# JACart2.net
KiCad netlist of a schematic drawn in EAGLE
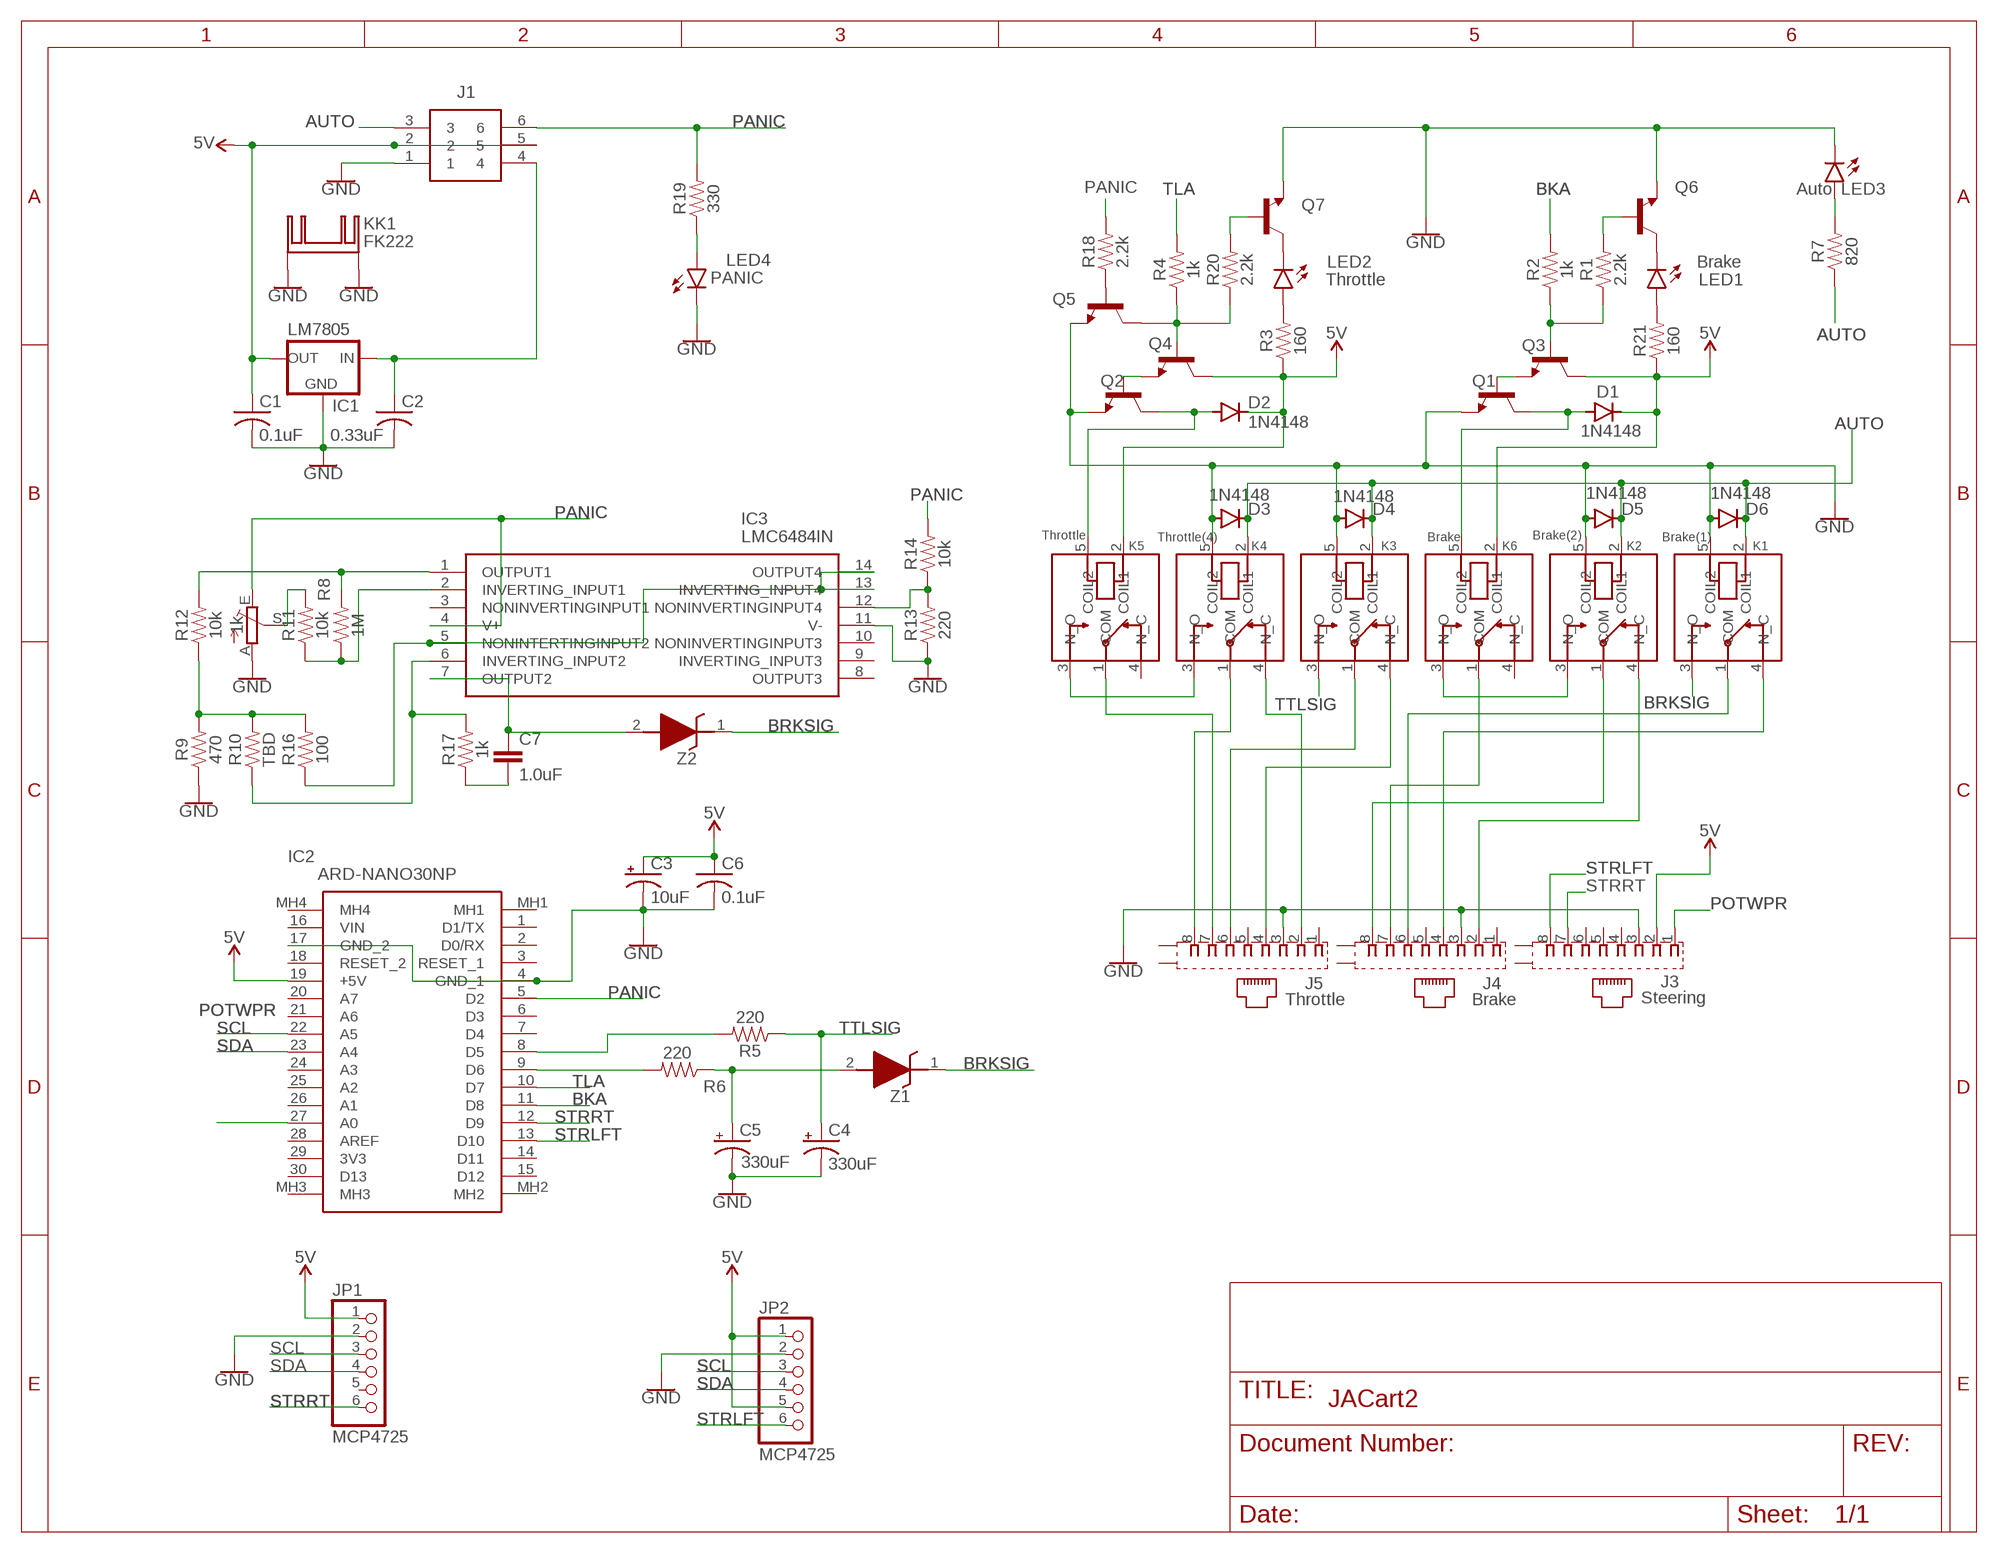
[diagram p0: schematic, sheet 1]

(export (version "E")
  (design (tool "Eeschema 10.0.6"))
  (components
    (comp (ref "C1")
      (value "0.1uF")
      (footprint "eagle-import:C050-024X044")
      (libsource (lib "eagle-import") (part "C-US050-024X044"))
    )
    (comp (ref "C2")
      (value "0.33uF")
      (footprint "eagle-import:C050-024X044")
      (libsource (lib "eagle-import") (part "C-US050-024X044"))
    )
    (comp (ref "C3")
      (value "10uF")
      (footprint "eagle-import:CPOL-RADIAL-2.5MM-5MM")
      (libsource (lib "eagle-import") (part "10UF-POLAR-RADIAL-2.5MM-25V-20%"))
    )
    (comp (ref "C4")
      (value "330uF")
      (footprint "eagle-import:PANASONIC_A")
      (libsource (lib "eagle-import") (part "330UF-PA"))
    )
    (comp (ref "C5")
      (value "330uF")
      (footprint "eagle-import:PANASONIC_A")
      (libsource (lib "eagle-import") (part "330UF-PA"))
    )
    (comp (ref "C6")
      (value "0.1uF")
      (footprint "eagle-import:C050-024X044")
      (fields (field (name "C6") "0.1uF"))
      (libsource (lib "eagle-import") (part "C-US050-024X044"))
    )
    (comp (ref "C7")
      (value "1.0uF")
      (footprint "eagle-import:CAP-PTH-SMALL-KIT")
      (libsource (lib "eagle-import") (part "0.1UF-KIT-EZ-50V-20%"))
    )
    (comp (ref "D1")
      (value "1N4148")
      (footprint "eagle-import:DO35-7")
      (libsource (lib "eagle-import") (part "1N4148DO35-7"))
    )
    (comp (ref "D2")
      (value "1N4148")
      (footprint "eagle-import:DO35-7")
      (libsource (lib "eagle-import") (part "1N4148DO35-7"))
    )
    (comp (ref "D3")
      (value "1N4148")
      (footprint "eagle-import:DO35-7")
      (libsource (lib "eagle-import") (part "1N4148DO35-7"))
    )
    (comp (ref "D4")
      (value "1N4148")
      (footprint "eagle-import:DO35-7")
      (libsource (lib "eagle-import") (part "1N4148DO35-7"))
    )
    (comp (ref "D5")
      (value "1N4148")
      (footprint "eagle-import:DO35-7")
      (libsource (lib "eagle-import") (part "1N4148DO35-7"))
    )
    (comp (ref "D6")
      (value "1N4148")
      (footprint "eagle-import:DO35-7")
      (libsource (lib "eagle-import") (part "1N4148DO35-7"))
    )
    (comp (ref "IC1")
      (value "LM7805")
      (footprint "eagle-import:78XXS")
      (libsource (lib "eagle-import") (part "7805-VR"))
    )
    (comp (ref "IC2")
      (value "ARD-NANO30NP")
      (footprint "eagle-import:ARDNANO30NP")
      (fields (field (name "MOUSER_PART_NUMBER") "992-ARD-NANO30NP"))
      (libsource (lib "eagle-import") (part "ARD-NANO30NP"))
    )
    (comp (ref "IC3")
      (value "LMC6484IN")
      (footprint "eagle-import:DIP794W56P254L1905H533Q14N")
      (fields (field (name "MOUSER_PART_NUMBER") "926-LMC6484IN"))
      (libsource (lib "eagle-import") (part "LMC6484IN"))
    )
    (comp (ref "J1")
      (value "39-30-1060")
      (footprint "eagle-import:39-30-1060_1")
      (fields (field (name "MOUSER_PART_NUMBER") "538-39-30-1060"))
      (libsource (lib "eagle-import") (part "39-30-1060"))
    )
    (comp (ref "J3")
      (value "Steering")
      (footprint "eagle-import:GLX-S-88M")
      (libsource (lib "eagle-import") (part "RJ45-RTANGL"))
    )
    (comp (ref "J4")
      (value "Brake")
      (footprint "eagle-import:GLX-S-88M")
      (fields (field (name "MF") "J4"))
      (libsource (lib "eagle-import") (part "RJ45-RTANGL"))
    )
    (comp (ref "J5")
      (value "Throttle")
      (footprint "eagle-import:GLX-S-88M")
      (libsource (lib "eagle-import") (part "RJ45-RTANGL"))
    )
    (comp (ref "JP1")
      (value "MCP4725")
      (footprint "eagle-import:1X06_ROUND_70")
      (libsource (lib "eagle-import") (part "HEADER-1X670MIL"))
    )
    (comp (ref "JP2")
      (value "MCP4725")
      (footprint "eagle-import:1X06_ROUND_70")
      (libsource (lib "eagle-import") (part "HEADER-1X670MIL"))
    )
    (comp (ref "K1")
      (value "Brake(1)")
      (footprint "eagle-import:RELAY_JS1-5V-F")
      (fields (field (name "MF") "Panasonic Electric") (field (name "MP") "JS1-5V-F"))
      (libsource (lib "eagle-import") (part "RELAY-SPDT"))
    )
    (comp (ref "K2")
      (value "Brake(2)")
      (footprint "eagle-import:RELAY_JS1-5V-F")
      (fields (field (name "MF") "Panasonic Electric") (field (name "MP") "JS1-5V-F"))
      (libsource (lib "eagle-import") (part "RELAY-SPDT"))
    )
    (comp (ref "K3")
      (value "Throttle(3)")
      (footprint "eagle-import:RELAY_JS1-5V-F")
      (fields (field (name "MF") "Panasonic Electric") (field (name "MP") "JS1-5V-F"))
      (libsource (lib "eagle-import") (part "RELAY-SPDT"))
    )
    (comp (ref "K4")
      (value "Throttle(4)")
      (footprint "eagle-import:RELAY_JS1-5V-F")
      (fields (field (name "MF") "Panasonic Electric") (field (name "MP") "JS1-5V-F"))
      (libsource (lib "eagle-import") (part "RELAY-SPDT"))
    )
    (comp (ref "K5")
      (value "Throttle")
      (footprint "eagle-import:RELAY_JS1-5V-F")
      (fields (field (name "MF") "Panasonic Electric") (field (name "MP") "JS1-5V-F"))
      (libsource (lib "eagle-import") (part "RELAY-SPDT"))
    )
    (comp (ref "K6")
      (value "Brake")
      (footprint "eagle-import:RELAY_JS1-5V-F")
      (fields (field (name "MF") "Panasonic Electric") (field (name "MP") "JS1-5V-F"))
      (libsource (lib "eagle-import") (part "RELAY-SPDT"))
    )
    (comp (ref "KK1")
      (value "FK222")
      (footprint "eagle-import:FK222")
      (libsource (lib "eagle-import") (part "FK222"))
    )
    (comp (ref "LED1")
      (value "Brake")
      (footprint "eagle-import:LED_5MM")
      (libsource (lib "eagle-import") (part "LED5MM"))
    )
    (comp (ref "LED2")
      (value "Throttle")
      (footprint "eagle-import:LED_5MM")
      (libsource (lib "eagle-import") (part "LED5MM"))
    )
    (comp (ref "LED3")
      (value "Auto")
      (footprint "eagle-import:LED_5MM")
      (libsource (lib "eagle-import") (part "LED5MM"))
    )
    (comp (ref "LED4")
      (value "PANIC")
      (footprint "eagle-import:LED_5MM")
      (libsource (lib "eagle-import") (part "LED5MM"))
    )
    (comp (ref "Q1")
      (value "2N3904")
      (footprint "eagle-import:TO92")
      (libsource (lib "eagle-import") (part "2N3904"))
    )
    (comp (ref "Q2")
      (value "2N3904")
      (footprint "eagle-import:TO92")
      (libsource (lib "eagle-import") (part "2N3904"))
    )
    (comp (ref "Q3")
      (value "2N3904")
      (footprint "eagle-import:TO92")
      (libsource (lib "eagle-import") (part "2N3904"))
    )
    (comp (ref "Q4")
      (value "2N3904")
      (footprint "eagle-import:TO92")
      (libsource (lib "eagle-import") (part "2N3904"))
    )
    (comp (ref "Q5")
      (value "2N3904")
      (footprint "eagle-import:TO92")
      (libsource (lib "eagle-import") (part "2N3904"))
    )
    (comp (ref "Q6")
      (value "2N3904")
      (footprint "eagle-import:TO92")
      (libsource (lib "eagle-import") (part "2N3904"))
    )
    (comp (ref "Q7")
      (value "2N3904")
      (footprint "eagle-import:TO92")
      (libsource (lib "eagle-import") (part "2N3904"))
    )
    (comp (ref "R1")
      (value "2.2k")
      (footprint "eagle-import:AXIAL-0.3")
      (libsource (lib "eagle-import") (part "RESISTORAXIAL-0.3"))
    )
    (comp (ref "R2")
      (value "1k")
      (footprint "eagle-import:AXIAL-0.3")
      (libsource (lib "eagle-import") (part "RESISTORAXIAL-0.3"))
    )
    (comp (ref "R3")
      (value "160")
      (footprint "eagle-import:AXIAL-0.3")
      (libsource (lib "eagle-import") (part "RESISTORAXIAL-0.3"))
    )
    (comp (ref "R4")
      (value "1k")
      (footprint "eagle-import:AXIAL-0.3")
      (libsource (lib "eagle-import") (part "RESISTORAXIAL-0.3"))
    )
    (comp (ref "R5")
      (value "220")
      (footprint "eagle-import:AXIAL-0.3")
      (libsource (lib "eagle-import") (part "RESISTORAXIAL-0.3"))
    )
    (comp (ref "R6")
      (value "220")
      (footprint "eagle-import:AXIAL-0.3")
      (libsource (lib "eagle-import") (part "RESISTORAXIAL-0.3"))
    )
    (comp (ref "R7")
      (value "820")
      (footprint "eagle-import:AXIAL-0.3")
      (libsource (lib "eagle-import") (part "RESISTORAXIAL-0.3"))
    )
    (comp (ref "R8")
      (value "1M")
      (footprint "eagle-import:AXIAL-0.3")
      (libsource (lib "eagle-import") (part "RESISTORAXIAL-0.3"))
    )
    (comp (ref "R9")
      (value "470")
      (footprint "eagle-import:AXIAL-0.3")
      (libsource (lib "eagle-import") (part "RESISTORAXIAL-0.3"))
    )
    (comp (ref "R10")
      (value "TBD")
      (footprint "eagle-import:AXIAL-0.3")
      (libsource (lib "eagle-import") (part "RESISTORAXIAL-0.3"))
    )
    (comp (ref "R11")
      (value "10k")
      (footprint "eagle-import:AXIAL-0.3")
      (libsource (lib "eagle-import") (part "RESISTORAXIAL-0.3"))
    )
    (comp (ref "R12")
      (value "10k")
      (footprint "eagle-import:AXIAL-0.3")
      (libsource (lib "eagle-import") (part "RESISTORAXIAL-0.3"))
    )
    (comp (ref "R13")
      (value "220")
      (footprint "eagle-import:AXIAL-0.3")
      (libsource (lib "eagle-import") (part "RESISTORAXIAL-0.3"))
    )
    (comp (ref "R14")
      (value "10k")
      (footprint "eagle-import:AXIAL-0.3")
      (libsource (lib "eagle-import") (part "RESISTORAXIAL-0.3"))
    )
    (comp (ref "R15")
      (value "1k")
      (footprint "eagle-import:RJ9W")
      (libsource (lib "eagle-import") (part "TRIM_EU-RJ9W"))
    )
    (comp (ref "R16")
      (value "100")
      (footprint "eagle-import:AXIAL-0.3")
      (libsource (lib "eagle-import") (part "RESISTORAXIAL-0.3"))
    )
    (comp (ref "R17")
      (value "1k")
      (footprint "eagle-import:AXIAL-0.3")
      (libsource (lib "eagle-import") (part "RESISTORAXIAL-0.3"))
    )
    (comp (ref "R18")
      (value "2.2k")
      (footprint "eagle-import:AXIAL-0.3")
      (libsource (lib "eagle-import") (part "RESISTORAXIAL-0.3"))
    )
    (comp (ref "R19")
      (value "330")
      (footprint "eagle-import:AXIAL-0.3")
      (libsource (lib "eagle-import") (part "RESISTORAXIAL-0.3"))
    )
    (comp (ref "R20")
      (value "2.2k")
      (footprint "eagle-import:AXIAL-0.3")
      (libsource (lib "eagle-import") (part "RESISTORAXIAL-0.3"))
    )
    (comp (ref "R21")
      (value "160")
      (footprint "eagle-import:AXIAL-0.3")
      (libsource (lib "eagle-import") (part "RESISTORAXIAL-0.3"))
    )
    (comp (ref "Z1")
      (value "BAT85S-TR")
      (footprint "eagle-import:DIOAD950W60L350D150")
      (fields (field (name "MOUSER_PART_NUMBER") "78-BAT85S"))
      (libsource (lib "eagle-import") (part "BAT85S-TR"))
    )
    (comp (ref "Z2")
      (value "BAT85S-TR")
      (footprint "eagle-import:DIOAD950W60L350D150")
      (fields (field (name "MOUSER_PART_NUMBER") "78-BAT85S"))
      (libsource (lib "eagle-import") (part "BAT85S-TR"))
    )
  )
  (nets
    (net (code "1") (name "/AUTO") (class "Default")
      (node (ref "D3") (pin "C") (pinfunction "C_C") (pintype "passive"))
      (node (ref "D4") (pin "C") (pinfunction "C_C") (pintype "passive"))
      (node (ref "D5") (pin "C") (pinfunction "C_C") (pintype "passive"))
      (node (ref "D6") (pin "C") (pinfunction "C_C") (pintype "passive"))
      (node (ref "J1") (pin "3") (pinfunction "3_3") (pintype "bidirectional"))
      (node (ref "K1") (pin "2") (pinfunction "COIL1_2") (pintype "passive"))
      (node (ref "K2") (pin "2") (pinfunction "COIL1_2") (pintype "passive"))
      (node (ref "K3") (pin "2") (pinfunction "COIL1_2") (pintype "passive"))
      (node (ref "K4") (pin "2") (pinfunction "COIL1_2") (pintype "passive"))
      (node (ref "R7") (pin "P$1") (pinfunction "1_P$1") (pintype "passive"))
    )
    (net (code "2") (name "/BKA") (class "Default")
      (node (ref "IC2") (pin "11") (pinfunction "D8_11") (pintype "bidirectional"))
      (node (ref "R2") (pin "P$2") (pinfunction "2_P$2") (pintype "passive"))
    )
    (net (code "3") (name "/BRKSIG") (class "Default")
      (node (ref "K1") (pin "3") (pinfunction "N_O_3") (pintype "passive"))
      (node (ref "Z1") (pin "1") (pinfunction "K_1") (pintype "bidirectional"))
      (node (ref "Z2") (pin "1") (pinfunction "K_1") (pintype "bidirectional"))
    )
    (net (code "4") (name "/PANIC") (class "Default")
      (node (ref "IC2") (pin "5") (pinfunction "D2_5") (pintype "bidirectional"))
      (node (ref "IC3") (pin "4") (pinfunction "V+_4") (pintype "bidirectional"))
      (node (ref "J1") (pin "6") (pinfunction "6_6") (pintype "bidirectional"))
      (node (ref "R14") (pin "P$2") (pinfunction "2_P$2") (pintype "passive"))
      (node (ref "R15") (pin "E") (pinfunction "E_E") (pintype "passive"))
      (node (ref "R18") (pin "P$2") (pinfunction "2_P$2") (pintype "passive"))
      (node (ref "R19") (pin "P$2") (pinfunction "2_P$2") (pintype "passive"))
    )
    (net (code "5") (name "/POTWPR") (class "Default")
      (node (ref "IC2") (pin "27") (pinfunction "A0_27") (pintype "bidirectional"))
      (node (ref "J3") (pin "1") (pinfunction "1_1") (pintype "passive"))
    )
    (net (code "6") (name "/SCL") (class "Default")
      (node (ref "IC2") (pin "22") (pinfunction "A5_22") (pintype "bidirectional"))
      (node (ref "JP1") (pin "3") (pinfunction "3_3") (pintype "passive"))
      (node (ref "JP2") (pin "3") (pinfunction "3_3") (pintype "passive"))
    )
    (net (code "7") (name "/SDA") (class "Default")
      (node (ref "IC2") (pin "23") (pinfunction "A4_23") (pintype "bidirectional"))
      (node (ref "JP1") (pin "4") (pinfunction "4_4") (pintype "passive"))
      (node (ref "JP2") (pin "4") (pinfunction "4_4") (pintype "passive"))
    )
    (net (code "8") (name "/STRLFT") (class "Default")
      (node (ref "IC2") (pin "13") (pinfunction "D10_13") (pintype "bidirectional"))
      (node (ref "J3") (pin "8") (pinfunction "8_8") (pintype "passive"))
      (node (ref "JP2") (pin "6") (pinfunction "6_6") (pintype "passive"))
    )
    (net (code "9") (name "/STRRT") (class "Default")
      (node (ref "IC2") (pin "12") (pinfunction "D9_12") (pintype "bidirectional"))
      (node (ref "J3") (pin "7") (pinfunction "7_7") (pintype "passive"))
      (node (ref "JP1") (pin "6") (pinfunction "6_6") (pintype "passive"))
    )
    (net (code "10") (name "/TLA") (class "Default")
      (node (ref "IC2") (pin "10") (pinfunction "D7_10") (pintype "bidirectional"))
      (node (ref "R4") (pin "P$2") (pinfunction "2_P$2") (pintype "passive"))
    )
    (net (code "11") (name "/TTLSIG") (class "Default")
      (node (ref "C4") (pin "+") (pinfunction "+_+") (pintype "passive"))
      (node (ref "K3") (pin "3") (pinfunction "N_O_3") (pintype "passive"))
      (node (ref "R5") (pin "P$1") (pinfunction "1_P$1") (pintype "passive"))
    )
    (net (code "12") (name "5V") (class "Default")
      (node (ref "C1") (pin "1") (pinfunction "1_1") (pintype "passive"))
      (node (ref "C3") (pin "1") (pinfunction "+_1") (pintype "passive"))
      (node (ref "C6") (pin "1") (pinfunction "1_1") (pintype "passive"))
      (node (ref "D1") (pin "C") (pinfunction "C_C") (pintype "passive"))
      (node (ref "D2") (pin "C") (pinfunction "C_C") (pintype "passive"))
      (node (ref "IC1") (pin "OUT") (pinfunction "OUT_OUT") (pintype "passive"))
      (node (ref "IC2") (pin "19") (pinfunction "+5V_19") (pintype "bidirectional"))
      (node (ref "J1") (pin "2") (pinfunction "2_2") (pintype "bidirectional"))
      (node (ref "J1") (pin "5") (pinfunction "5_5") (pintype "bidirectional"))
      (node (ref "J3") (pin "2") (pinfunction "2_2") (pintype "passive"))
      (node (ref "JP1") (pin "1") (pinfunction "1_1") (pintype "passive"))
      (node (ref "JP2") (pin "1") (pinfunction "1_1") (pintype "passive"))
      (node (ref "JP2") (pin "5") (pinfunction "5_5") (pintype "passive"))
      (node (ref "K5") (pin "2") (pinfunction "COIL1_2") (pintype "passive"))
      (node (ref "K6") (pin "2") (pinfunction "COIL1_2") (pintype "passive"))
      (node (ref "Q3") (pin "1") (pinfunction "C_1") (pintype "passive"))
      (node (ref "Q4") (pin "1") (pinfunction "C_1") (pintype "passive"))
      (node (ref "R21") (pin "P$1") (pinfunction "1_P$1") (pintype "passive"))
      (node (ref "R3") (pin "P$1") (pinfunction "1_P$1") (pintype "passive"))
    )
    (net (code "13") (name "GND") (class "Default")
      (node (ref "C1") (pin "2") (pinfunction "2_2") (pintype "passive"))
      (node (ref "C2") (pin "2") (pinfunction "2_2") (pintype "passive"))
      (node (ref "C3") (pin "2") (pinfunction "-_2") (pintype "passive"))
      (node (ref "C4") (pin "-") (pinfunction "-_-") (pintype "passive"))
      (node (ref "C5") (pin "-") (pinfunction "-_-") (pintype "passive"))
      (node (ref "C6") (pin "2") (pinfunction "2_2") (pintype "passive"))
      (node (ref "D3") (pin "A") (pinfunction "A_A") (pintype "passive"))
      (node (ref "D4") (pin "A") (pinfunction "A_A") (pintype "passive"))
      (node (ref "D5") (pin "A") (pinfunction "A_A") (pintype "passive"))
      (node (ref "D6") (pin "A") (pinfunction "A_A") (pintype "passive"))
      (node (ref "IC1") (pin "GND") (pinfunction "GND_GND") (pintype "input"))
      (node (ref "IC2") (pin "17") (pinfunction "GND_2_17") (pintype "bidirectional"))
      (node (ref "IC2") (pin "4") (pinfunction "GND_1_4") (pintype "bidirectional"))
      (node (ref "IC3") (pin "11") (pinfunction "V-_11") (pintype "bidirectional"))
      (node (ref "J1") (pin "1") (pinfunction "1_1") (pintype "bidirectional"))
      (node (ref "J3") (pin "3") (pinfunction "3_3") (pintype "passive"))
      (node (ref "J4") (pin "3") (pinfunction "3_3") (pintype "passive"))
      (node (ref "J5") (pin "3") (pinfunction "3_3") (pintype "passive"))
      (node (ref "JP1") (pin "2") (pinfunction "2_2") (pintype "passive"))
      (node (ref "JP2") (pin "2") (pinfunction "2_2") (pintype "passive"))
      (node (ref "K1") (pin "5") (pinfunction "COIL2_5") (pintype "passive"))
      (node (ref "K2") (pin "5") (pinfunction "COIL2_5") (pintype "passive"))
      (node (ref "K3") (pin "5") (pinfunction "COIL2_5") (pintype "passive"))
      (node (ref "K4") (pin "5") (pinfunction "COIL2_5") (pintype "passive"))
      (node (ref "KK1") (pin "A2,8") (pinfunction "K_A2,8") (pintype "passive"))
      (node (ref "KK1") (pin "B2,8") (pinfunction "K_B2,8") (pintype "passive"))
      (node (ref "LED3") (pin "K") (pinfunction "C_K") (pintype "passive"))
      (node (ref "LED4") (pin "K") (pinfunction "C_K") (pintype "passive"))
      (node (ref "Q1") (pin "3") (pinfunction "E_3") (pintype "passive"))
      (node (ref "Q2") (pin "3") (pinfunction "E_3") (pintype "passive"))
      (node (ref "Q5") (pin "3") (pinfunction "E_3") (pintype "passive"))
      (node (ref "Q6") (pin "3") (pinfunction "E_3") (pintype "passive"))
      (node (ref "Q7") (pin "3") (pinfunction "E_3") (pintype "passive"))
      (node (ref "R13") (pin "P$1") (pinfunction "1_P$1") (pintype "passive"))
      (node (ref "R15") (pin "A") (pinfunction "A_A") (pintype "passive"))
      (node (ref "R9") (pin "P$1") (pinfunction "1_P$1") (pintype "passive"))
    )
    (net (code "14") (name "Net-(C2-Pad1)") (class "Default")
      (node (ref "C2") (pin "1") (pinfunction "1_1") (pintype "passive"))
      (node (ref "IC1") (pin "IN") (pinfunction "IN_IN") (pintype "input"))
      (node (ref "J1") (pin "4") (pinfunction "4_4") (pintype "bidirectional"))
    )
    (net (code "15") (name "Net-(IC2-D5)") (class "Default")
      (node (ref "IC2") (pin "8") (pinfunction "D5_8") (pintype "bidirectional"))
      (node (ref "R5") (pin "P$2") (pinfunction "2_P$2") (pintype "passive"))
    )
    (net (code "16") (name "Net-(IC2-D6)") (class "Default")
      (node (ref "IC2") (pin "9") (pinfunction "D6_9") (pintype "bidirectional"))
      (node (ref "R6") (pin "P$2") (pinfunction "2_P$2") (pintype "passive"))
    )
    (net (code "17") (name "Net-(IC3-INVERTING_INPUT1)") (class "Default")
      (node (ref "IC3") (pin "2") (pinfunction "INVERTING_INPUT1_2") (pintype "bidirectional"))
      (node (ref "R11") (pin "P$1") (pinfunction "1_P$1") (pintype "passive"))
      (node (ref "R8") (pin "P$1") (pinfunction "1_P$1") (pintype "passive"))
    )
    (net (code "18") (name "Net-(IC3-INVERTING_INPUT2)") (class "Default")
      (node (ref "IC3") (pin "6") (pinfunction "INVERTING_INPUT2_6") (pintype "bidirectional"))
      (node (ref "R10") (pin "P$1") (pinfunction "1_P$1") (pintype "passive"))
      (node (ref "R17") (pin "P$2") (pinfunction "2_P$2") (pintype "passive"))
    )
    (net (code "19") (name "Net-(IC3-INVERTING_INPUT4)") (class "Default")
      (node (ref "IC3") (pin "13") (pinfunction "INVERTING_INPUT4_13") (pintype "bidirectional"))
      (node (ref "IC3") (pin "14") (pinfunction "OUTPUT4_14") (pintype "bidirectional"))
      (node (ref "IC3") (pin "5") (pinfunction "NONINTERTINGINPUT2_5") (pintype "bidirectional"))
      (node (ref "R16") (pin "P$1") (pinfunction "1_P$1") (pintype "passive"))
    )
    (net (code "20") (name "Net-(IC3-NONINVERTINGINPUT4)") (class "Default")
      (node (ref "IC3") (pin "12") (pinfunction "NONINVERTINGINPUT4_12") (pintype "bidirectional"))
      (node (ref "R13") (pin "P$2") (pinfunction "2_P$2") (pintype "passive"))
      (node (ref "R14") (pin "P$1") (pinfunction "1_P$1") (pintype "passive"))
    )
    (net (code "21") (name "Net-(IC3-OUTPUT1)") (class "Default")
      (node (ref "IC3") (pin "1") (pinfunction "OUTPUT1_1") (pintype "bidirectional"))
      (node (ref "R12") (pin "P$2") (pinfunction "2_P$2") (pintype "passive"))
      (node (ref "R8") (pin "P$2") (pinfunction "2_P$2") (pintype "passive"))
    )
    (net (code "22") (name "Net-(IC3-OUTPUT2)") (class "Default")
      (node (ref "C7") (pin "1") (pinfunction "1_1") (pintype "passive"))
      (node (ref "IC3") (pin "7") (pinfunction "OUTPUT2_7") (pintype "bidirectional"))
      (node (ref "Z2") (pin "2") (pinfunction "A_2") (pintype "bidirectional"))
    )
    (net (code "23") (name "Net-(K1-COM)") (class "Default")
      (node (ref "J4") (pin "6") (pinfunction "6_6") (pintype "passive"))
      (node (ref "K1") (pin "1") (pinfunction "COM_1") (pintype "passive"))
    )
    (net (code "24") (name "Net-(K1-N_C)") (class "Default")
      (node (ref "J4") (pin "4") (pinfunction "4_4") (pintype "passive"))
      (node (ref "K1") (pin "4") (pinfunction "N_C_4") (pintype "passive"))
    )
    (net (code "25") (name "Net-(K2-COM)") (class "Default")
      (node (ref "J4") (pin "8") (pinfunction "8_8") (pintype "passive"))
      (node (ref "K2") (pin "1") (pinfunction "COM_1") (pintype "passive"))
    )
    (net (code "26") (name "Net-(K2-N_C)") (class "Default")
      (node (ref "J4") (pin "2") (pinfunction "2_2") (pintype "passive"))
      (node (ref "K2") (pin "4") (pinfunction "N_C_4") (pintype "passive"))
    )
    (net (code "27") (name "Net-(K2-N_O)") (class "Default")
      (node (ref "K2") (pin "3") (pinfunction "N_O_3") (pintype "passive"))
      (node (ref "K6") (pin "3") (pinfunction "N_O_3") (pintype "passive"))
    )
    (net (code "28") (name "Net-(K3-COM)") (class "Default")
      (node (ref "J5") (pin "6") (pinfunction "6_6") (pintype "passive"))
      (node (ref "K3") (pin "1") (pinfunction "COM_1") (pintype "passive"))
    )
    (net (code "29") (name "Net-(K3-N_C)") (class "Default")
      (node (ref "J5") (pin "4") (pinfunction "4_4") (pintype "passive"))
      (node (ref "K3") (pin "4") (pinfunction "N_C_4") (pintype "passive"))
    )
    (net (code "30") (name "Net-(K4-COM)") (class "Default")
      (node (ref "J5") (pin "8") (pinfunction "8_8") (pintype "passive"))
      (node (ref "K4") (pin "1") (pinfunction "COM_1") (pintype "passive"))
    )
    (net (code "31") (name "Net-(K4-N_C)") (class "Default")
      (node (ref "J5") (pin "2") (pinfunction "2_2") (pintype "passive"))
      (node (ref "K4") (pin "4") (pinfunction "N_C_4") (pintype "passive"))
    )
    (net (code "32") (name "Net-(K4-N_O)") (class "Default")
      (node (ref "K4") (pin "3") (pinfunction "N_O_3") (pintype "passive"))
      (node (ref "K5") (pin "3") (pinfunction "N_O_3") (pintype "passive"))
    )
    (net (code "33") (name "Net-(K5-COIL2)") (class "Default")
      (node (ref "D2") (pin "A") (pinfunction "A_A") (pintype "passive"))
      (node (ref "K5") (pin "5") (pinfunction "COIL2_5") (pintype "passive"))
      (node (ref "Q2") (pin "1") (pinfunction "C_1") (pintype "passive"))
    )
    (net (code "34") (name "Net-(K5-COM)") (class "Default")
      (node (ref "J5") (pin "7") (pinfunction "7_7") (pintype "passive"))
      (node (ref "K5") (pin "1") (pinfunction "COM_1") (pintype "passive"))
    )
    (net (code "35") (name "Net-(K6-COIL2)") (class "Default")
      (node (ref "D1") (pin "A") (pinfunction "A_A") (pintype "passive"))
      (node (ref "K6") (pin "5") (pinfunction "COIL2_5") (pintype "passive"))
      (node (ref "Q1") (pin "1") (pinfunction "C_1") (pintype "passive"))
    )
    (net (code "36") (name "Net-(K6-COM)") (class "Default")
      (node (ref "J4") (pin "7") (pinfunction "7_7") (pintype "passive"))
      (node (ref "K6") (pin "1") (pinfunction "COM_1") (pintype "passive"))
    )
    (net (code "37") (name "Net-(LED1-C)") (class "Default")
      (node (ref "LED1") (pin "K") (pinfunction "C_K") (pintype "passive"))
      (node (ref "Q6") (pin "1") (pinfunction "C_1") (pintype "passive"))
    )
    (net (code "38") (name "Net-(LED2-C)") (class "Default")
      (node (ref "LED2") (pin "K") (pinfunction "C_K") (pintype "passive"))
      (node (ref "Q7") (pin "1") (pinfunction "C_1") (pintype "passive"))
    )
    (net (code "39") (name "Net-(Q1-B)") (class "Default")
      (node (ref "Q1") (pin "2") (pinfunction "B_2") (pintype "passive"))
      (node (ref "Q3") (pin "3") (pinfunction "E_3") (pintype "passive"))
    )
    (net (code "40") (name "Net-(Q2-B)") (class "Default")
      (node (ref "Q2") (pin "2") (pinfunction "B_2") (pintype "passive"))
      (node (ref "Q4") (pin "3") (pinfunction "E_3") (pintype "passive"))
    )
    (net (code "41") (name "Net-(Q3-B)") (class "Default")
      (node (ref "Q3") (pin "2") (pinfunction "B_2") (pintype "passive"))
      (node (ref "R1") (pin "P$1") (pinfunction "1_P$1") (pintype "passive"))
      (node (ref "R2") (pin "P$1") (pinfunction "1_P$1") (pintype "passive"))
    )
    (net (code "42") (name "Net-(Q4-B)") (class "Default")
      (node (ref "Q4") (pin "2") (pinfunction "B_2") (pintype "passive"))
      (node (ref "Q5") (pin "1") (pinfunction "C_1") (pintype "passive"))
      (node (ref "R20") (pin "P$1") (pinfunction "1_P$1") (pintype "passive"))
      (node (ref "R4") (pin "P$1") (pinfunction "1_P$1") (pintype "passive"))
    )
    (net (code "43") (name "Net-(Q5-B)") (class "Default")
      (node (ref "Q5") (pin "2") (pinfunction "B_2") (pintype "passive"))
      (node (ref "R18") (pin "P$1") (pinfunction "1_P$1") (pintype "passive"))
    )
    (net (code "44") (name "Net-(Q6-B)") (class "Default")
      (node (ref "Q6") (pin "2") (pinfunction "B_2") (pintype "passive"))
      (node (ref "R1") (pin "P$2") (pinfunction "2_P$2") (pintype "passive"))
    )
    (net (code "45") (name "Net-(Q7-B)") (class "Default")
      (node (ref "Q7") (pin "2") (pinfunction "B_2") (pintype "passive"))
      (node (ref "R20") (pin "P$2") (pinfunction "2_P$2") (pintype "passive"))
    )
    (net (code "46") (name "Net-(R3-2)") (class "Default")
      (node (ref "LED2") (pin "A") (pinfunction "A_A") (pintype "passive"))
      (node (ref "R3") (pin "P$2") (pinfunction "2_P$2") (pintype "passive"))
    )
    (net (code "47") (name "Net-(R6-1)") (class "Default")
      (node (ref "C5") (pin "+") (pinfunction "+_+") (pintype "passive"))
      (node (ref "R6") (pin "P$1") (pinfunction "1_P$1") (pintype "passive"))
      (node (ref "Z1") (pin "2") (pinfunction "A_2") (pintype "bidirectional"))
    )
    (net (code "48") (name "Net-(R7-2)") (class "Default")
      (node (ref "LED3") (pin "A") (pinfunction "A_A") (pintype "passive"))
      (node (ref "R7") (pin "P$2") (pinfunction "2_P$2") (pintype "passive"))
    )
    (net (code "49") (name "Net-(R10-2)") (class "Default")
      (node (ref "R10") (pin "P$2") (pinfunction "2_P$2") (pintype "passive"))
      (node (ref "R12") (pin "P$1") (pinfunction "1_P$1") (pintype "passive"))
      (node (ref "R16") (pin "P$2") (pinfunction "2_P$2") (pintype "passive"))
      (node (ref "R9") (pin "P$2") (pinfunction "2_P$2") (pintype "passive"))
    )
    (net (code "50") (name "Net-(R11-2)") (class "Default")
      (node (ref "R11") (pin "P$2") (pinfunction "2_P$2") (pintype "passive"))
      (node (ref "R15") (pin "S") (pinfunction "S_S") (pintype "passive"))
    )
    (net (code "51") (name "Net-(R17-1)") (class "Default")
      (node (ref "C7") (pin "2") (pinfunction "2_2") (pintype "passive"))
      (node (ref "R17") (pin "P$1") (pinfunction "1_P$1") (pintype "passive"))
    )
    (net (code "52") (name "Net-(R19-1)") (class "Default")
      (node (ref "LED4") (pin "A") (pinfunction "A_A") (pintype "passive"))
      (node (ref "R19") (pin "P$1") (pinfunction "1_P$1") (pintype "passive"))
    )
    (net (code "53") (name "Net-(R21-2)") (class "Default")
      (node (ref "LED1") (pin "A") (pinfunction "A_A") (pintype "passive"))
      (node (ref "R21") (pin "P$2") (pinfunction "2_P$2") (pintype "passive"))
    )
    (net (code "54") (name "unconnected-(IC2-3V3-Pad29)") (class "Default")
      (node (ref "IC2") (pin "29") (pinfunction "3V3_29") (pintype "bidirectional"))
    )
    (net (code "55") (name "unconnected-(IC2-A1-Pad26)") (class "Default")
      (node (ref "IC2") (pin "26") (pinfunction "A1_26") (pintype "bidirectional"))
    )
    (net (code "56") (name "unconnected-(IC2-A2-Pad25)") (class "Default")
      (node (ref "IC2") (pin "25") (pinfunction "A2_25") (pintype "bidirectional"))
    )
    (net (code "57") (name "unconnected-(IC2-A3-Pad24)") (class "Default")
      (node (ref "IC2") (pin "24") (pinfunction "A3_24") (pintype "bidirectional"))
    )
    (net (code "58") (name "unconnected-(IC2-A6-Pad21)") (class "Default")
      (node (ref "IC2") (pin "21") (pinfunction "A6_21") (pintype "bidirectional"))
    )
    (net (code "59") (name "unconnected-(IC2-A7-Pad20)") (class "Default")
      (node (ref "IC2") (pin "20") (pinfunction "A7_20") (pintype "bidirectional"))
    )
    (net (code "60") (name "unconnected-(IC2-AREF-Pad28)") (class "Default")
      (node (ref "IC2") (pin "28") (pinfunction "AREF_28") (pintype "bidirectional"))
    )
    (net (code "61") (name "unconnected-(IC2-D0{slash}RX-Pad2)") (class "Default")
      (node (ref "IC2") (pin "2") (pinfunction "D0/RX_2") (pintype "bidirectional"))
    )
    (net (code "62") (name "unconnected-(IC2-D1{slash}TX-Pad1)") (class "Default")
      (node (ref "IC2") (pin "1") (pinfunction "D1/TX_1") (pintype "bidirectional"))
    )
    (net (code "63") (name "unconnected-(IC2-D3-Pad6)") (class "Default")
      (node (ref "IC2") (pin "6") (pinfunction "D3_6") (pintype "bidirectional"))
    )
    (net (code "64") (name "unconnected-(IC2-D4-Pad7)") (class "Default")
      (node (ref "IC2") (pin "7") (pinfunction "D4_7") (pintype "bidirectional"))
    )
    (net (code "65") (name "unconnected-(IC2-D11-Pad14)") (class "Default")
      (node (ref "IC2") (pin "14") (pinfunction "D11_14") (pintype "bidirectional"))
    )
    (net (code "66") (name "unconnected-(IC2-D12-Pad15)") (class "Default")
      (node (ref "IC2") (pin "15") (pinfunction "D12_15") (pintype "bidirectional"))
    )
    (net (code "67") (name "unconnected-(IC2-D13-Pad30)") (class "Default")
      (node (ref "IC2") (pin "30") (pinfunction "D13_30") (pintype "bidirectional"))
    )
    (net (code "68") (name "unconnected-(IC2-PadMH1)") (class "Default")
      (node (ref "IC2") (pin "MH1") (pinfunction "MH1_MH1") (pintype "bidirectional"))
    )
    (net (code "69") (name "unconnected-(IC2-PadMH2)") (class "Default")
      (node (ref "IC2") (pin "MH2") (pinfunction "MH2_MH2") (pintype "bidirectional"))
    )
    (net (code "70") (name "unconnected-(IC2-PadMH3)") (class "Default")
      (node (ref "IC2") (pin "MH3") (pinfunction "MH3_MH3") (pintype "bidirectional"))
    )
    (net (code "71") (name "unconnected-(IC2-PadMH4)") (class "Default")
      (node (ref "IC2") (pin "MH4") (pinfunction "MH4_MH4") (pintype "bidirectional"))
    )
    (net (code "72") (name "unconnected-(IC2-RESET_1-Pad3)") (class "Default")
      (node (ref "IC2") (pin "3") (pinfunction "RESET_1_3") (pintype "bidirectional"))
    )
    (net (code "73") (name "unconnected-(IC2-RESET_2-Pad18)") (class "Default")
      (node (ref "IC2") (pin "18") (pinfunction "RESET_2_18") (pintype "bidirectional"))
    )
    (net (code "74") (name "unconnected-(IC2-VIN-Pad16)") (class "Default")
      (node (ref "IC2") (pin "16") (pinfunction "VIN_16") (pintype "bidirectional"))
    )
    (net (code "75") (name "unconnected-(IC3-INVERTING_INPUT3-Pad9)") (class "Default")
      (node (ref "IC3") (pin "9") (pinfunction "INVERTING_INPUT3_9") (pintype "bidirectional"))
    )
    (net (code "76") (name "unconnected-(IC3-NONINVERTINGINPUT1-Pad3)") (class "Default")
      (node (ref "IC3") (pin "3") (pinfunction "NONINVERTINGINPUT1_3") (pintype "bidirectional"))
    )
    (net (code "77") (name "unconnected-(IC3-NONINVERTINGINPUT3-Pad10)") (class "Default")
      (node (ref "IC3") (pin "10") (pinfunction "NONINVERTINGINPUT3_10") (pintype "bidirectional"))
    )
    (net (code "78") (name "unconnected-(IC3-OUTPUT3-Pad8)") (class "Default")
      (node (ref "IC3") (pin "8") (pinfunction "OUTPUT3_8") (pintype "bidirectional"))
    )
    (net (code "79") (name "unconnected-(J3-Pad4)") (class "Default")
      (node (ref "J3") (pin "4") (pinfunction "4_4") (pintype "passive"))
    )
    (net (code "80") (name "unconnected-(J3-Pad5)") (class "Default")
      (node (ref "J3") (pin "5") (pinfunction "5_5") (pintype "passive"))
    )
    (net (code "81") (name "unconnected-(J3-Pad6)") (class "Default")
      (node (ref "J3") (pin "6") (pinfunction "6_6") (pintype "passive"))
    )
    (net (code "82") (name "unconnected-(J3-PadS1)") (class "Default")
      (node (ref "J3") (pin "S1") (pinfunction "S1_S1") (pintype "passive"))
    )
    (net (code "83") (name "unconnected-(J3-PadS2)") (class "Default")
      (node (ref "J3") (pin "S2") (pinfunction "S2_S2") (pintype "passive"))
    )
    (net (code "84") (name "unconnected-(J4-Pad1)") (class "Default")
      (node (ref "J4") (pin "1") (pinfunction "1_1") (pintype "passive"))
    )
    (net (code "85") (name "unconnected-(J4-Pad5)") (class "Default")
      (node (ref "J4") (pin "5") (pinfunction "5_5") (pintype "passive"))
    )
    (net (code "86") (name "unconnected-(J4-PadS1)") (class "Default")
      (node (ref "J4") (pin "S1") (pinfunction "S1_S1") (pintype "passive"))
    )
    (net (code "87") (name "unconnected-(J4-PadS2)") (class "Default")
      (node (ref "J4") (pin "S2") (pinfunction "S2_S2") (pintype "passive"))
    )
    (net (code "88") (name "unconnected-(J5-Pad1)") (class "Default")
      (node (ref "J5") (pin "1") (pinfunction "1_1") (pintype "passive"))
    )
    (net (code "89") (name "unconnected-(J5-Pad5)") (class "Default")
      (node (ref "J5") (pin "5") (pinfunction "5_5") (pintype "passive"))
    )
    (net (code "90") (name "unconnected-(J5-PadS1)") (class "Default")
      (node (ref "J5") (pin "S1") (pinfunction "S1_S1") (pintype "passive"))
    )
    (net (code "91") (name "unconnected-(J5-PadS2)") (class "Default")
      (node (ref "J5") (pin "S2") (pinfunction "S2_S2") (pintype "passive"))
    )
    (net (code "92") (name "unconnected-(JP1-Pad5)") (class "Default")
      (node (ref "JP1") (pin "5") (pinfunction "5_5") (pintype "passive"))
    )
    (net (code "93") (name "unconnected-(K5-N_C-Pad4)") (class "Default")
      (node (ref "K5") (pin "4") (pinfunction "N_C_4") (pintype "passive"))
    )
    (net (code "94") (name "unconnected-(K6-N_C-Pad4)") (class "Default")
      (node (ref "K6") (pin "4") (pinfunction "N_C_4") (pintype "passive"))
    )
  )
)
